# gate_boost.net
KiCad netlist of a schematic drawn in EAGLE
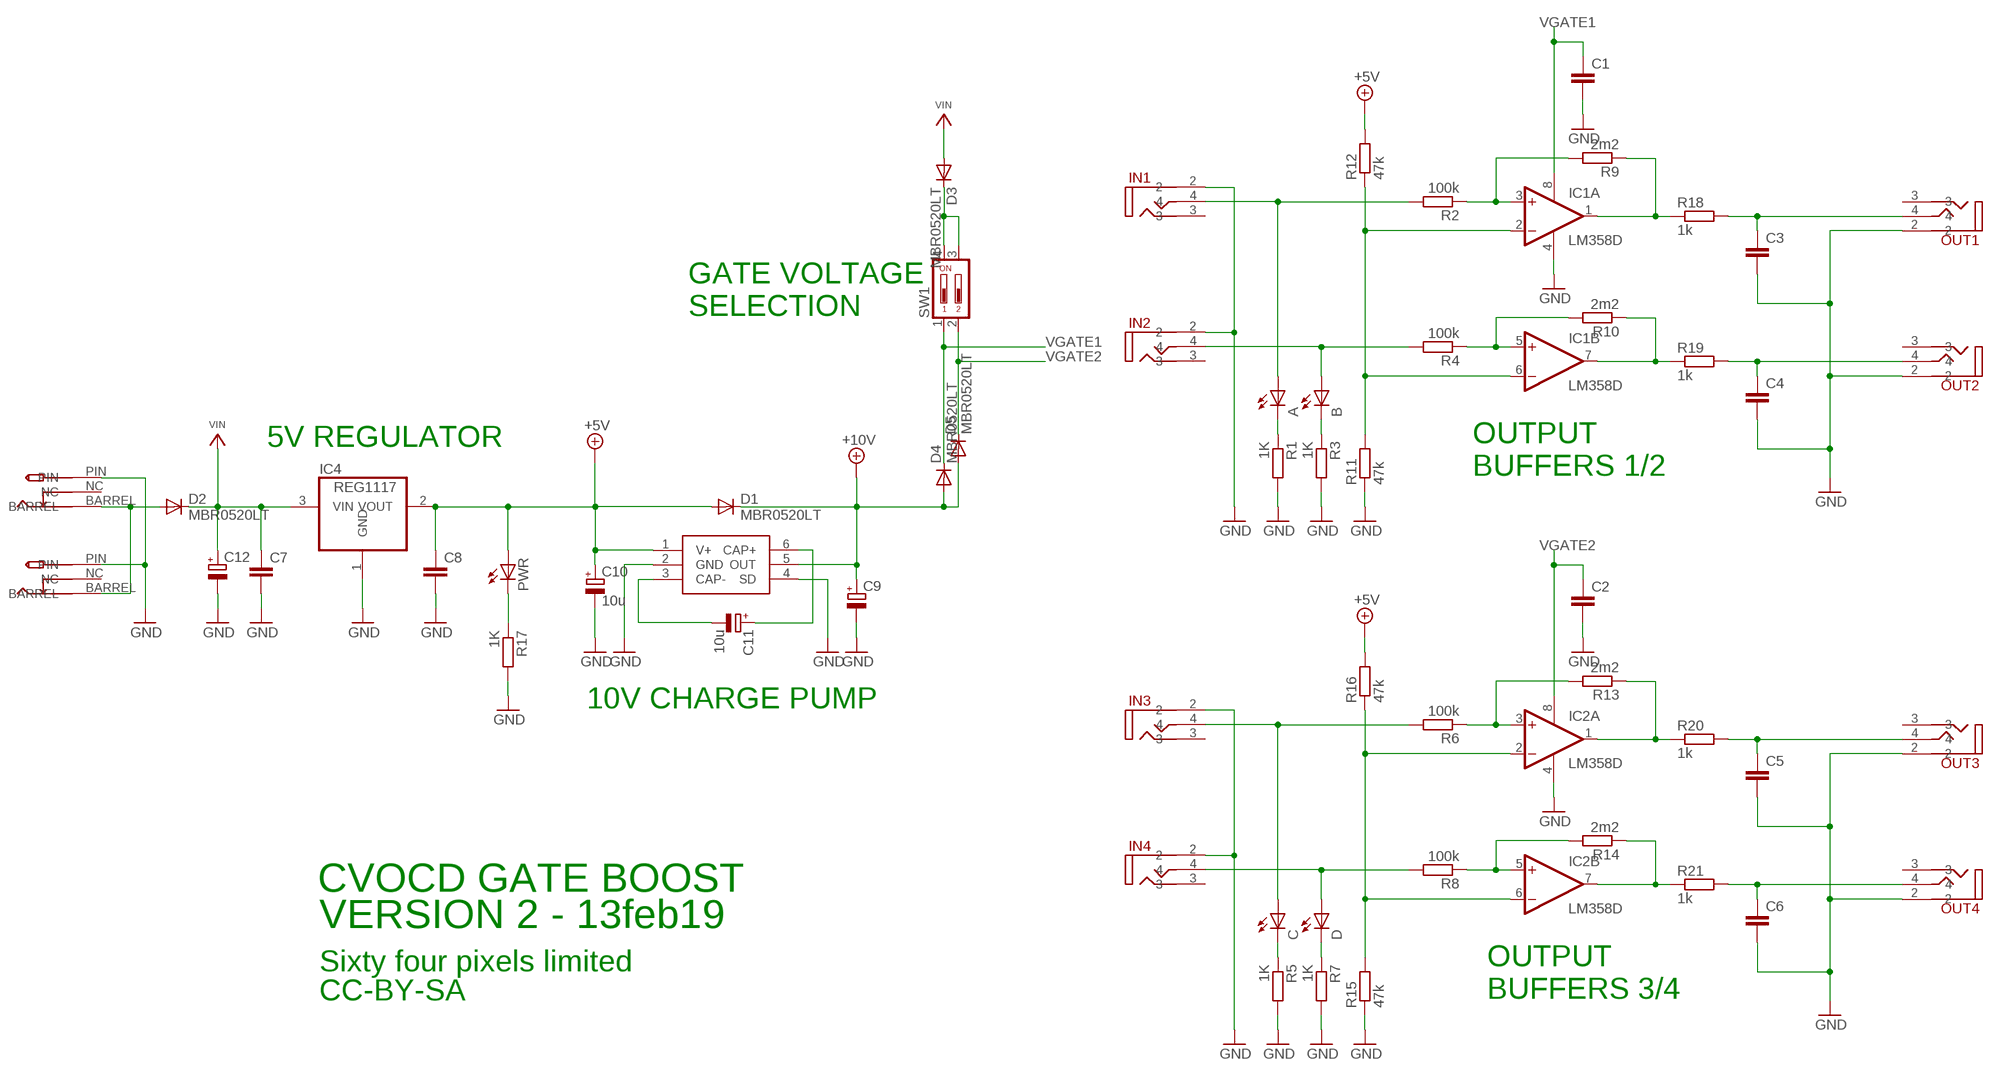
[diagram p0: schematic, sheet 1]

(export (version "E")
  (design (tool "Eeschema 10.0.6"))
  (components
    (comp (ref "A")
      (value "LED3MM")
      (footprint "eagle-import:LED3MM")
      (libsource (lib "eagle-import") (part "LED3MM"))
    )
    (comp (ref "B")
      (value "LED3MM")
      (footprint "eagle-import:LED3MM")
      (libsource (lib "eagle-import") (part "LED3MM"))
    )
    (comp (ref "C")
      (value "LED3MM")
      (footprint "eagle-import:LED3MM")
      (libsource (lib "eagle-import") (part "LED3MM"))
    )
    (comp (ref "C1")
      (value "C-EUC0805")
      (footprint "eagle-import:C0805")
      (libsource (lib "eagle-import") (part "C-EUC0805"))
    )
    (comp (ref "C2")
      (value "C-EUC0805")
      (footprint "eagle-import:C0805")
      (libsource (lib "eagle-import") (part "C-EUC0805"))
    )
    (comp (ref "C3")
      (value "C-EUC0805")
      (footprint "eagle-import:C0805")
      (libsource (lib "eagle-import") (part "C-EUC0805"))
    )
    (comp (ref "C4")
      (value "C-EUC0805")
      (footprint "eagle-import:C0805")
      (libsource (lib "eagle-import") (part "C-EUC0805"))
    )
    (comp (ref "C5")
      (value "C-EUC0805")
      (footprint "eagle-import:C0805")
      (libsource (lib "eagle-import") (part "C-EUC0805"))
    )
    (comp (ref "C6")
      (value "C-EUC0805")
      (footprint "eagle-import:C0805")
      (libsource (lib "eagle-import") (part "C-EUC0805"))
    )
    (comp (ref "C7")
      (value "C-EUC0805")
      (footprint "eagle-import:C0805")
      (libsource (lib "eagle-import") (part "C-EUC0805"))
    )
    (comp (ref "C8")
      (value "C-EUC0805")
      (footprint "eagle-import:C0805")
      (libsource (lib "eagle-import") (part "C-EUC0805"))
    )
    (comp (ref "C9")
      (value "CPOL-EUSMCA")
      (footprint "eagle-import:SMC_A")
      (libsource (lib "eagle-import") (part "CPOL-EUSMCA"))
    )
    (comp (ref "C10")
      (value "10u")
      (footprint "eagle-import:SMC_A")
      (libsource (lib "eagle-import") (part "CPOL-EUSMCA"))
    )
    (comp (ref "C11")
      (value "10u")
      (footprint "eagle-import:SMC_A")
      (libsource (lib "eagle-import") (part "CPOL-EUSMCA"))
    )
    (comp (ref "C12")
      (value "CPOL-EUE2-5")
      (footprint "eagle-import:E2-5")
      (libsource (lib "eagle-import") (part "CPOL-EUE2-5"))
    )
    (comp (ref "D")
      (value "LED3MM")
      (footprint "eagle-import:LED3MM")
      (libsource (lib "eagle-import") (part "LED3MM"))
    )
    (comp (ref "D1")
      (value "MBR0520LT")
      (footprint "eagle-import:SOD123")
      (libsource (lib "eagle-import") (part "MBR0520LT"))
    )
    (comp (ref "D2")
      (value "MBR0520LT")
      (footprint "eagle-import:SOD123")
      (libsource (lib "eagle-import") (part "MBR0520LT"))
    )
    (comp (ref "D3")
      (value "MBR0520LT")
      (footprint "eagle-import:SOD123")
      (libsource (lib "eagle-import") (part "MBR0520LT"))
    )
    (comp (ref "D4")
      (value "MBR0520LT")
      (footprint "eagle-import:SOD123")
      (libsource (lib "eagle-import") (part "MBR0520LT"))
    )
    (comp (ref "D5")
      (value "MBR0520LT")
      (footprint "eagle-import:SOD123")
      (libsource (lib "eagle-import") (part "MBR0520LT"))
    )
    (comp (ref "IC1")
      (value "LM358D")
      (footprint "eagle-import:SO08")
      (libsource (lib "eagle-import") (part "LM358D"))
    )
    (comp (ref "IC2")
      (value "LM358D")
      (footprint "eagle-import:SO08")
      (libsource (lib "eagle-import") (part "LM358D"))
    )
    (comp (ref "IC3")
      (value "LM27675M5_CHARGEPUMP")
      (footprint "eagle-import:SOT23-6")
      (libsource (lib "eagle-import") (part "LM27675M5_CHARGEPUMP"))
    )
    (comp (ref "IC4")
      (value "REG1117")
      (footprint "eagle-import:SOT223")
      (libsource (lib "eagle-import") (part "REG1117"))
    )
    (comp (ref "IN1")
      (value "VERTICAL_3_5MM_SOCKET")
      (footprint "eagle-import:VERTICAL_3_5MM_SOCKET")
      (libsource (lib "eagle-import") (part "VERTICAL_3_5MM_SOCKET"))
    )
    (comp (ref "IN2")
      (value "VERTICAL_3_5MM_SOCKET")
      (footprint "eagle-import:VERTICAL_3_5MM_SOCKET")
      (libsource (lib "eagle-import") (part "VERTICAL_3_5MM_SOCKET"))
    )
    (comp (ref "IN3")
      (value "VERTICAL_3_5MM_SOCKET")
      (footprint "eagle-import:VERTICAL_3_5MM_SOCKET")
      (libsource (lib "eagle-import") (part "VERTICAL_3_5MM_SOCKET"))
    )
    (comp (ref "IN4")
      (value "VERTICAL_3_5MM_SOCKET")
      (footprint "eagle-import:VERTICAL_3_5MM_SOCKET")
      (libsource (lib "eagle-import") (part "VERTICAL_3_5MM_SOCKET"))
    )
    (comp (ref "OUT1")
      (value "VERTICAL_3_5MM_SOCKET")
      (footprint "eagle-import:VERTICAL_3_5MM_SOCKET")
      (libsource (lib "eagle-import") (part "VERTICAL_3_5MM_SOCKET"))
    )
    (comp (ref "OUT2")
      (value "VERTICAL_3_5MM_SOCKET")
      (footprint "eagle-import:VERTICAL_3_5MM_SOCKET")
      (libsource (lib "eagle-import") (part "VERTICAL_3_5MM_SOCKET"))
    )
    (comp (ref "OUT3")
      (value "VERTICAL_3_5MM_SOCKET")
      (footprint "eagle-import:VERTICAL_3_5MM_SOCKET")
      (libsource (lib "eagle-import") (part "VERTICAL_3_5MM_SOCKET"))
    )
    (comp (ref "OUT4")
      (value "VERTICAL_3_5MM_SOCKET")
      (footprint "eagle-import:VERTICAL_3_5MM_SOCKET")
      (libsource (lib "eagle-import") (part "VERTICAL_3_5MM_SOCKET"))
    )
    (comp (ref "PWR")
      (value "LED3MM")
      (footprint "eagle-import:LED3MM")
      (libsource (lib "eagle-import") (part "LED3MM"))
    )
    (comp (ref "R1")
      (value "1K")
      (footprint "eagle-import:R0805")
      (libsource (lib "eagle-import") (part "R-EU_R0805"))
    )
    (comp (ref "R2")
      (value "100k")
      (footprint "eagle-import:R0805")
      (libsource (lib "eagle-import") (part "R-EU_R0805"))
    )
    (comp (ref "R3")
      (value "1K")
      (footprint "eagle-import:R0805")
      (libsource (lib "eagle-import") (part "R-EU_R0805"))
    )
    (comp (ref "R4")
      (value "100k")
      (footprint "eagle-import:R0805")
      (libsource (lib "eagle-import") (part "R-EU_R0805"))
    )
    (comp (ref "R5")
      (value "1K")
      (footprint "eagle-import:R0805")
      (libsource (lib "eagle-import") (part "R-EU_R0805"))
    )
    (comp (ref "R6")
      (value "100k")
      (footprint "eagle-import:R0805")
      (libsource (lib "eagle-import") (part "R-EU_R0805"))
    )
    (comp (ref "R7")
      (value "1K")
      (footprint "eagle-import:R0805")
      (libsource (lib "eagle-import") (part "R-EU_R0805"))
    )
    (comp (ref "R8")
      (value "100k")
      (footprint "eagle-import:R0805")
      (libsource (lib "eagle-import") (part "R-EU_R0805"))
    )
    (comp (ref "R9")
      (value "2m2")
      (footprint "eagle-import:R0805")
      (libsource (lib "eagle-import") (part "R-EU_R0805"))
    )
    (comp (ref "R10")
      (value "2m2")
      (footprint "eagle-import:R0805")
      (libsource (lib "eagle-import") (part "R-EU_R0805"))
    )
    (comp (ref "R11")
      (value "47k")
      (footprint "eagle-import:R0805")
      (libsource (lib "eagle-import") (part "R-EU_R0805"))
    )
    (comp (ref "R12")
      (value "47k")
      (footprint "eagle-import:R0805")
      (libsource (lib "eagle-import") (part "R-EU_R0805"))
    )
    (comp (ref "R13")
      (value "2m2")
      (footprint "eagle-import:R0805")
      (libsource (lib "eagle-import") (part "R-EU_R0805"))
    )
    (comp (ref "R14")
      (value "2m2")
      (footprint "eagle-import:R0805")
      (libsource (lib "eagle-import") (part "R-EU_R0805"))
    )
    (comp (ref "R15")
      (value "47k")
      (footprint "eagle-import:R0805")
      (libsource (lib "eagle-import") (part "R-EU_R0805"))
    )
    (comp (ref "R16")
      (value "47k")
      (footprint "eagle-import:R0805")
      (libsource (lib "eagle-import") (part "R-EU_R0805"))
    )
    (comp (ref "R17")
      (value "1K")
      (footprint "eagle-import:R0805")
      (libsource (lib "eagle-import") (part "R-EU_R0805"))
    )
    (comp (ref "R18")
      (value "1k")
      (footprint "eagle-import:R0805")
      (libsource (lib "eagle-import") (part "R-EU_R0805"))
    )
    (comp (ref "R19")
      (value "1k")
      (footprint "eagle-import:R0805")
      (libsource (lib "eagle-import") (part "R-EU_R0805"))
    )
    (comp (ref "R20")
      (value "1k")
      (footprint "eagle-import:R0805")
      (libsource (lib "eagle-import") (part "R-EU_R0805"))
    )
    (comp (ref "R21")
      (value "1k")
      (footprint "eagle-import:R0805")
      (libsource (lib "eagle-import") (part "R-EU_R0805"))
    )
    (comp (ref "SW1")
      (value "DIP02YL")
      (footprint "eagle-import:DIP02YL")
      (libsource (lib "eagle-import") (part "DIP02YL"))
    )
    (comp (ref "U$1")
      (value "PWR_SOCKET_2_1MM")
      (footprint "eagle-import:PWR_SOCKET_2_1MM")
      (libsource (lib "eagle-import") (part "PWR_SOCKET_2_1MM"))
    )
    (comp (ref "U$2")
      (value "PWR_SOCKET_2_1MM")
      (footprint "eagle-import:PWR_SOCKET_2_1MM")
      (libsource (lib "eagle-import") (part "PWR_SOCKET_2_1MM"))
    )
  )
  (nets
    (net (code "1") (name "+5V") (class "Default")
      (node (ref "C10") (pin "+") (pinfunction "+_+") (pintype "passive"))
      (node (ref "C8") (pin "1") (pinfunction "1_1") (pintype "passive"))
      (node (ref "D1") (pin "A") (pinfunction "A_A") (pintype "passive"))
      (node (ref "IC3") (pin "1") (pinfunction "V+_1") (pintype "bidirectional"))
      (node (ref "IC4") (pin "2") (pinfunction "VOUT_2") (pintype "output"))
      (node (ref "PWR") (pin "A") (pinfunction "A_A") (pintype "passive"))
      (node (ref "R12") (pin "2") (pinfunction "2_2") (pintype "passive"))
      (node (ref "R16") (pin "2") (pinfunction "2_2") (pintype "passive"))
    )
    (net (code "2") (name "+10V") (class "Default")
      (node (ref "C9") (pin "+") (pinfunction "+_+") (pintype "passive"))
      (node (ref "D1") (pin "C") (pinfunction "C_C") (pintype "passive"))
      (node (ref "D4") (pin "A") (pinfunction "A_A") (pintype "passive"))
      (node (ref "D5") (pin "A") (pinfunction "A_A") (pintype "passive"))
      (node (ref "IC3") (pin "5") (pinfunction "OUT_5") (pintype "bidirectional"))
    )
    (net (code "3") (name "/VGATE1") (class "Default")
      (node (ref "C1") (pin "1") (pinfunction "1_1") (pintype "passive"))
      (node (ref "D4") (pin "C") (pinfunction "C_C") (pintype "passive"))
      (node (ref "IC1") (pin "8") (pinfunction "V+_8") (pintype "power_in"))
      (node (ref "SW1") (pin "1") (pinfunction "1_1") (pintype "passive"))
    )
    (net (code "4") (name "/VGATE2") (class "Default")
      (node (ref "C2") (pin "1") (pinfunction "1_1") (pintype "passive"))
      (node (ref "D5") (pin "C") (pinfunction "C_C") (pintype "passive"))
      (node (ref "IC2") (pin "8") (pinfunction "V+_8") (pintype "power_in"))
      (node (ref "SW1") (pin "2") (pinfunction "2_2") (pintype "passive"))
    )
    (net (code "5") (name "GND") (class "Default")
      (node (ref "C1") (pin "2") (pinfunction "2_2") (pintype "passive"))
      (node (ref "C10") (pin "-") (pinfunction "-_-") (pintype "passive"))
      (node (ref "C12") (pin "-") (pinfunction "-_-") (pintype "passive"))
      (node (ref "C2") (pin "2") (pinfunction "2_2") (pintype "passive"))
      (node (ref "C3") (pin "2") (pinfunction "2_2") (pintype "passive"))
      (node (ref "C4") (pin "2") (pinfunction "2_2") (pintype "passive"))
      (node (ref "C5") (pin "2") (pinfunction "2_2") (pintype "passive"))
      (node (ref "C6") (pin "2") (pinfunction "2_2") (pintype "passive"))
      (node (ref "C7") (pin "2") (pinfunction "2_2") (pintype "passive"))
      (node (ref "C8") (pin "2") (pinfunction "2_2") (pintype "passive"))
      (node (ref "C9") (pin "-") (pinfunction "-_-") (pintype "passive"))
      (node (ref "IC1") (pin "4") (pinfunction "V-_4") (pintype "power_in"))
      (node (ref "IC2") (pin "4") (pinfunction "V-_4") (pintype "power_in"))
      (node (ref "IC3") (pin "2") (pinfunction "GND_2") (pintype "bidirectional"))
      (node (ref "IC3") (pin "4") (pinfunction "SD_4") (pintype "bidirectional"))
      (node (ref "IC4") (pin "1") (pinfunction "GND_1") (pintype "power_in"))
      (node (ref "IN1") (pin "2") (pinfunction "2_2") (pintype "bidirectional"))
      (node (ref "IN2") (pin "2") (pinfunction "2_2") (pintype "bidirectional"))
      (node (ref "IN3") (pin "2") (pinfunction "2_2") (pintype "bidirectional"))
      (node (ref "IN4") (pin "2") (pinfunction "2_2") (pintype "bidirectional"))
      (node (ref "OUT1") (pin "2") (pinfunction "2_2") (pintype "bidirectional"))
      (node (ref "OUT2") (pin "2") (pinfunction "2_2") (pintype "bidirectional"))
      (node (ref "OUT3") (pin "2") (pinfunction "2_2") (pintype "bidirectional"))
      (node (ref "OUT4") (pin "2") (pinfunction "2_2") (pintype "bidirectional"))
      (node (ref "R1") (pin "2") (pinfunction "2_2") (pintype "passive"))
      (node (ref "R11") (pin "1") (pinfunction "1_1") (pintype "passive"))
      (node (ref "R15") (pin "1") (pinfunction "1_1") (pintype "passive"))
      (node (ref "R17") (pin "2") (pinfunction "2_2") (pintype "passive"))
      (node (ref "R3") (pin "2") (pinfunction "2_2") (pintype "passive"))
      (node (ref "R5") (pin "2") (pinfunction "2_2") (pintype "passive"))
      (node (ref "R7") (pin "2") (pinfunction "2_2") (pintype "passive"))
      (node (ref "U$1") (pin "PIN") (pinfunction "PIN_PIN") (pintype "bidirectional"))
      (node (ref "U$2") (pin "PIN") (pinfunction "PIN_PIN") (pintype "bidirectional"))
    )
    (net (code "6") (name "Net-(A-C)") (class "Default")
      (node (ref "A") (pin "K") (pinfunction "C_K") (pintype "passive"))
      (node (ref "R1") (pin "1") (pinfunction "1_1") (pintype "passive"))
    )
    (net (code "7") (name "Net-(A-PadA)") (class "Default")
      (node (ref "A") (pin "A") (pinfunction "A_A") (pintype "passive"))
      (node (ref "IN1") (pin "4") (pinfunction "4_4") (pintype "bidirectional"))
      (node (ref "R2") (pin "2") (pinfunction "2_2") (pintype "passive"))
    )
    (net (code "8") (name "Net-(B-C)") (class "Default")
      (node (ref "B") (pin "K") (pinfunction "C_K") (pintype "passive"))
      (node (ref "R3") (pin "1") (pinfunction "1_1") (pintype "passive"))
    )
    (net (code "9") (name "Net-(B-PadA)") (class "Default")
      (node (ref "B") (pin "A") (pinfunction "A_A") (pintype "passive"))
      (node (ref "IN2") (pin "4") (pinfunction "4_4") (pintype "bidirectional"))
      (node (ref "R4") (pin "2") (pinfunction "2_2") (pintype "passive"))
    )
    (net (code "10") (name "Net-(C-C)") (class "Default")
      (node (ref "C") (pin "K") (pinfunction "C_K") (pintype "passive"))
      (node (ref "R5") (pin "1") (pinfunction "1_1") (pintype "passive"))
    )
    (net (code "11") (name "Net-(C-PadA)") (class "Default")
      (node (ref "C") (pin "A") (pinfunction "A_A") (pintype "passive"))
      (node (ref "IN3") (pin "4") (pinfunction "4_4") (pintype "bidirectional"))
      (node (ref "R6") (pin "2") (pinfunction "2_2") (pintype "passive"))
    )
    (net (code "12") (name "Net-(C3-Pad1)") (class "Default")
      (node (ref "C3") (pin "1") (pinfunction "1_1") (pintype "passive"))
      (node (ref "OUT1") (pin "4") (pinfunction "4_4") (pintype "bidirectional"))
      (node (ref "R18") (pin "2") (pinfunction "2_2") (pintype "passive"))
    )
    (net (code "13") (name "Net-(C4-Pad1)") (class "Default")
      (node (ref "C4") (pin "1") (pinfunction "1_1") (pintype "passive"))
      (node (ref "OUT2") (pin "4") (pinfunction "4_4") (pintype "bidirectional"))
      (node (ref "R19") (pin "2") (pinfunction "2_2") (pintype "passive"))
    )
    (net (code "14") (name "Net-(C5-Pad1)") (class "Default")
      (node (ref "C5") (pin "1") (pinfunction "1_1") (pintype "passive"))
      (node (ref "OUT3") (pin "4") (pinfunction "4_4") (pintype "bidirectional"))
      (node (ref "R20") (pin "2") (pinfunction "2_2") (pintype "passive"))
    )
    (net (code "15") (name "Net-(C6-Pad1)") (class "Default")
      (node (ref "C6") (pin "1") (pinfunction "1_1") (pintype "passive"))
      (node (ref "OUT4") (pin "4") (pinfunction "4_4") (pintype "bidirectional"))
      (node (ref "R21") (pin "2") (pinfunction "2_2") (pintype "passive"))
    )
    (net (code "16") (name "Net-(D-C)") (class "Default")
      (node (ref "D") (pin "K") (pinfunction "C_K") (pintype "passive"))
      (node (ref "R7") (pin "1") (pinfunction "1_1") (pintype "passive"))
    )
    (net (code "17") (name "Net-(D-PadA)") (class "Default")
      (node (ref "D") (pin "A") (pinfunction "A_A") (pintype "passive"))
      (node (ref "IN4") (pin "4") (pinfunction "4_4") (pintype "bidirectional"))
      (node (ref "R8") (pin "2") (pinfunction "2_2") (pintype "passive"))
    )
    (net (code "18") (name "Net-(D2-PadA)") (class "Default")
      (node (ref "D2") (pin "A") (pinfunction "A_A") (pintype "passive"))
      (node (ref "U$1") (pin "BARREL") (pinfunction "BARREL_BARREL") (pintype "bidirectional"))
      (node (ref "U$2") (pin "BARREL") (pinfunction "BARREL_BARREL") (pintype "bidirectional"))
    )
    (net (code "19") (name "Net-(D3-PadC)") (class "Default")
      (node (ref "D3") (pin "C") (pinfunction "C_C") (pintype "passive"))
      (node (ref "SW1") (pin "3") (pinfunction "3_3") (pintype "passive"))
      (node (ref "SW1") (pin "4") (pinfunction "4_4") (pintype "passive"))
    )
    (net (code "20") (name "Net-(IC1A-+IN)") (class "Default")
      (node (ref "IC1") (pin "3") (pinfunction "+IN_3") (pintype "input"))
      (node (ref "R2") (pin "1") (pinfunction "1_1") (pintype "passive"))
      (node (ref "R9") (pin "2") (pinfunction "2_2") (pintype "passive"))
    )
    (net (code "21") (name "Net-(IC1A--IN)") (class "Default")
      (node (ref "IC1") (pin "2") (pinfunction "-IN_2") (pintype "input"))
      (node (ref "IC1") (pin "6") (pinfunction "-IN_6") (pintype "input"))
      (node (ref "R11") (pin "2") (pinfunction "2_2") (pintype "passive"))
      (node (ref "R12") (pin "1") (pinfunction "1_1") (pintype "passive"))
    )
    (net (code "22") (name "Net-(IC1A-OUT)") (class "Default")
      (node (ref "IC1") (pin "1") (pinfunction "OUT_1") (pintype "output"))
      (node (ref "R18") (pin "1") (pinfunction "1_1") (pintype "passive"))
      (node (ref "R9") (pin "1") (pinfunction "1_1") (pintype "passive"))
    )
    (net (code "23") (name "Net-(IC1B-+IN)") (class "Default")
      (node (ref "IC1") (pin "5") (pinfunction "+IN_5") (pintype "input"))
      (node (ref "R10") (pin "2") (pinfunction "2_2") (pintype "passive"))
      (node (ref "R4") (pin "1") (pinfunction "1_1") (pintype "passive"))
    )
    (net (code "24") (name "Net-(IC1B-OUT)") (class "Default")
      (node (ref "IC1") (pin "7") (pinfunction "OUT_7") (pintype "output"))
      (node (ref "R10") (pin "1") (pinfunction "1_1") (pintype "passive"))
      (node (ref "R19") (pin "1") (pinfunction "1_1") (pintype "passive"))
    )
    (net (code "25") (name "Net-(IC2A-+IN)") (class "Default")
      (node (ref "IC2") (pin "3") (pinfunction "+IN_3") (pintype "input"))
      (node (ref "R13") (pin "2") (pinfunction "2_2") (pintype "passive"))
      (node (ref "R6") (pin "1") (pinfunction "1_1") (pintype "passive"))
    )
    (net (code "26") (name "Net-(IC2A--IN)") (class "Default")
      (node (ref "IC2") (pin "2") (pinfunction "-IN_2") (pintype "input"))
      (node (ref "IC2") (pin "6") (pinfunction "-IN_6") (pintype "input"))
      (node (ref "R15") (pin "2") (pinfunction "2_2") (pintype "passive"))
      (node (ref "R16") (pin "1") (pinfunction "1_1") (pintype "passive"))
    )
    (net (code "27") (name "Net-(IC2A-OUT)") (class "Default")
      (node (ref "IC2") (pin "1") (pinfunction "OUT_1") (pintype "output"))
      (node (ref "R13") (pin "1") (pinfunction "1_1") (pintype "passive"))
      (node (ref "R20") (pin "1") (pinfunction "1_1") (pintype "passive"))
    )
    (net (code "28") (name "Net-(IC2B-+IN)") (class "Default")
      (node (ref "IC2") (pin "5") (pinfunction "+IN_5") (pintype "input"))
      (node (ref "R14") (pin "2") (pinfunction "2_2") (pintype "passive"))
      (node (ref "R8") (pin "1") (pinfunction "1_1") (pintype "passive"))
    )
    (net (code "29") (name "Net-(IC2B-OUT)") (class "Default")
      (node (ref "IC2") (pin "7") (pinfunction "OUT_7") (pintype "output"))
      (node (ref "R14") (pin "1") (pinfunction "1_1") (pintype "passive"))
      (node (ref "R21") (pin "1") (pinfunction "1_1") (pintype "passive"))
    )
    (net (code "30") (name "Net-(IC3-CAP+)") (class "Default")
      (node (ref "C11") (pin "+") (pinfunction "+_+") (pintype "passive"))
      (node (ref "IC3") (pin "6") (pinfunction "CAP+_6") (pintype "bidirectional"))
    )
    (net (code "31") (name "Net-(IC3-CAP-)") (class "Default")
      (node (ref "C11") (pin "-") (pinfunction "-_-") (pintype "passive"))
      (node (ref "IC3") (pin "3") (pinfunction "CAP-_3") (pintype "bidirectional"))
    )
    (net (code "32") (name "Net-(PWR-C)") (class "Default")
      (node (ref "PWR") (pin "K") (pinfunction "C_K") (pintype "passive"))
      (node (ref "R17") (pin "1") (pinfunction "1_1") (pintype "passive"))
    )
    (net (code "33") (name "VIN") (class "Default")
      (node (ref "C12") (pin "+") (pinfunction "+_+") (pintype "passive"))
      (node (ref "C7") (pin "1") (pinfunction "1_1") (pintype "passive"))
      (node (ref "D2") (pin "C") (pinfunction "C_C") (pintype "passive"))
      (node (ref "D3") (pin "A") (pinfunction "A_A") (pintype "passive"))
      (node (ref "IC4") (pin "3") (pinfunction "VIN_3") (pintype "input"))
    )
    (net (code "34") (name "unconnected-(IN1-Pad3)") (class "Default")
      (node (ref "IN1") (pin "3") (pinfunction "3_3") (pintype "bidirectional"))
    )
    (net (code "35") (name "unconnected-(IN2-Pad3)") (class "Default")
      (node (ref "IN2") (pin "3") (pinfunction "3_3") (pintype "bidirectional"))
    )
    (net (code "36") (name "unconnected-(IN3-Pad3)") (class "Default")
      (node (ref "IN3") (pin "3") (pinfunction "3_3") (pintype "bidirectional"))
    )
    (net (code "37") (name "unconnected-(IN4-Pad3)") (class "Default")
      (node (ref "IN4") (pin "3") (pinfunction "3_3") (pintype "bidirectional"))
    )
    (net (code "38") (name "unconnected-(OUT1-Pad3)") (class "Default")
      (node (ref "OUT1") (pin "3") (pinfunction "3_3") (pintype "bidirectional"))
    )
    (net (code "39") (name "unconnected-(OUT2-Pad3)") (class "Default")
      (node (ref "OUT2") (pin "3") (pinfunction "3_3") (pintype "bidirectional"))
    )
    (net (code "40") (name "unconnected-(OUT3-Pad3)") (class "Default")
      (node (ref "OUT3") (pin "3") (pinfunction "3_3") (pintype "bidirectional"))
    )
    (net (code "41") (name "unconnected-(OUT4-Pad3)") (class "Default")
      (node (ref "OUT4") (pin "3") (pinfunction "3_3") (pintype "bidirectional"))
    )
    (net (code "42") (name "unconnected-(U$1-PadNC)") (class "Default")
      (node (ref "U$1") (pin "NC") (pinfunction "NC_NC") (pintype "bidirectional"))
    )
    (net (code "43") (name "unconnected-(U$2-PadNC)") (class "Default")
      (node (ref "U$2") (pin "NC") (pinfunction "NC_NC") (pintype "bidirectional"))
    )
  )
)
